# 04B-060.net
KiCad netlist of a schematic drawn in EAGLE
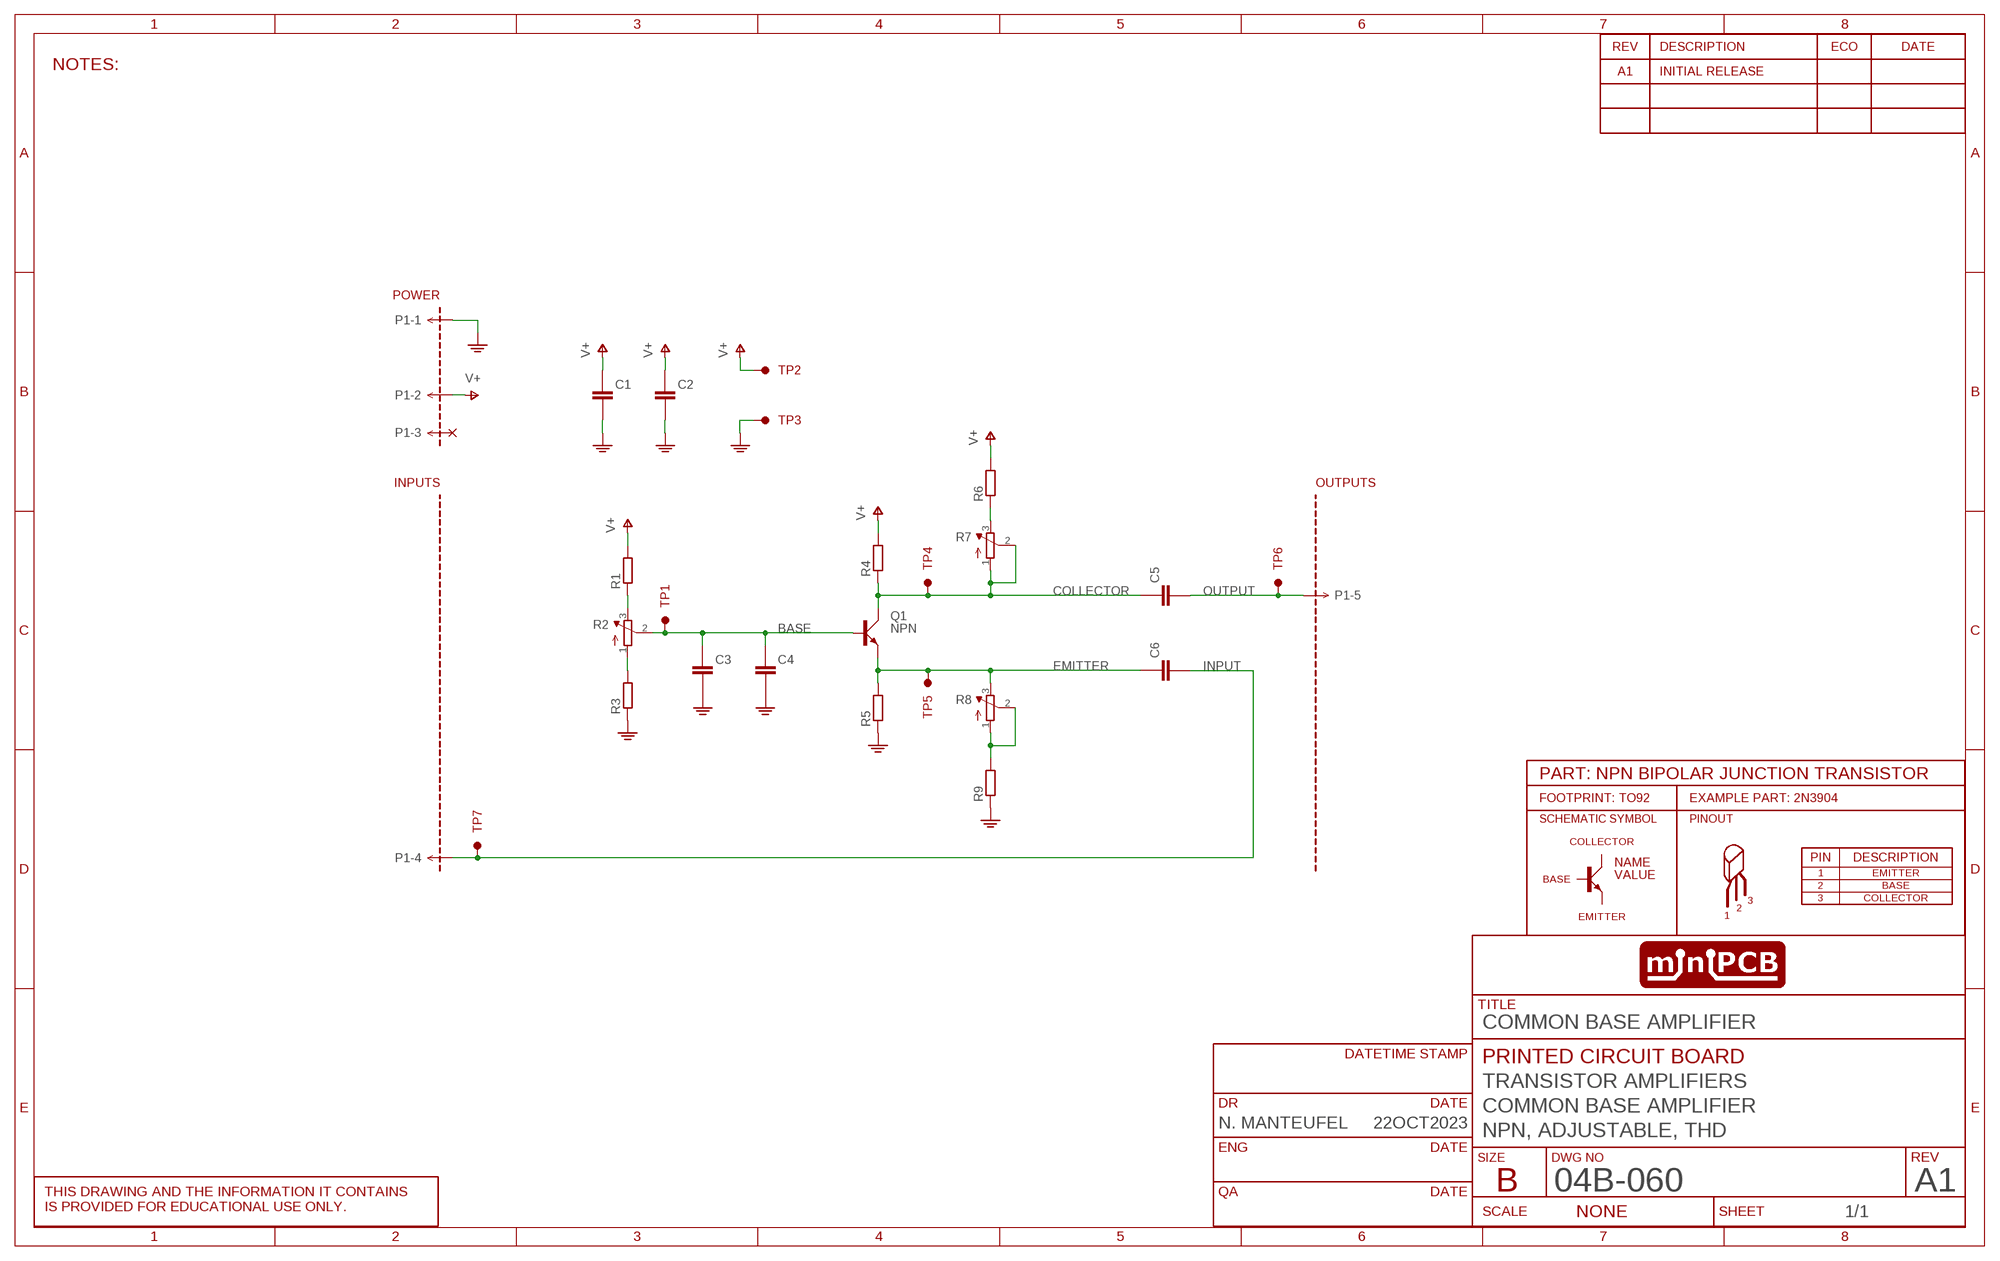
[diagram p0: schematic, sheet 1]

(export (version "E")
  (design (tool "Eeschema 10.0.6"))
  (components
    (comp (ref "C1")
      (value "CAPACITOR_10")
      (footprint "eagle-import:C5MM")
      (libsource (lib "eagle-import") (part "CAPACITOR_10"))
    )
    (comp (ref "C2")
      (value "CAPACITORTHD")
      (footprint "eagle-import:C050-024X044")
      (libsource (lib "eagle-import") (part "CAPACITORTHD"))
    )
    (comp (ref "C3")
      (value "CAPACITOR_10")
      (footprint "eagle-import:C5MM")
      (libsource (lib "eagle-import") (part "CAPACITOR_10"))
    )
    (comp (ref "C4")
      (value "CAPACITORTHD")
      (footprint "eagle-import:C050-024X044")
      (libsource (lib "eagle-import") (part "CAPACITORTHD"))
    )
    (comp (ref "C5")
      (value "CAPACITORTHD")
      (footprint "eagle-import:C050-024X044")
      (libsource (lib "eagle-import") (part "CAPACITORTHD"))
    )
    (comp (ref "C6")
      (value "CAPACITORTHD")
      (footprint "eagle-import:C050-024X044")
      (libsource (lib "eagle-import") (part "CAPACITORTHD"))
    )
    (comp (ref "P1")
      (value "MINIPCB_5P5P")
      (footprint "eagle-import:PINS_1X5")
      (libsource (lib "eagle-import") (part "MINIPCB_5P5P"))
    )
    (comp (ref "PCB1")
      (value "MINIPCB_0P50X50")
      (footprint "eagle-import:MINIPCB_0P_50X50MM")
      (fields
        (field (name "CIRCUIT_CATEGORY") "TRANSISTOR AMPLIFIERS")
        (field (name "PART_NUMBER") "04B-060")
        (field (name "REVISION") "A1-01")
        (field (name "TITLE") "COMMON BASE AMPLIFIER")
      )
      (libsource (lib "eagle-import") (part "MINIPCB_0P50X50"))
    )
    (comp (ref "Q1")
      (value "NPN")
      (footprint "eagle-import:TO92-EBC-OVAL")
      (libsource (lib "eagle-import") (part "BJT_NPNEBC"))
    )
    (comp (ref "R1")
      (value "RESISTORTHD")
      (footprint "eagle-import:0204_10")
      (libsource (lib "eagle-import") (part "RESISTORTHD"))
    )
    (comp (ref "R2")
      (value "TRIMPOT0.100THD")
      (footprint "eagle-import:TRIM_0100")
      (libsource (lib "eagle-import") (part "TRIMPOT0.100THD"))
    )
    (comp (ref "R3")
      (value "RESISTORTHD")
      (footprint "eagle-import:0204_10")
      (libsource (lib "eagle-import") (part "RESISTORTHD"))
    )
    (comp (ref "R4")
      (value "RESISTORTHD")
      (footprint "eagle-import:0204_10")
      (libsource (lib "eagle-import") (part "RESISTORTHD"))
    )
    (comp (ref "R5")
      (value "RESISTORTHD")
      (footprint "eagle-import:0204_10")
      (libsource (lib "eagle-import") (part "RESISTORTHD"))
    )
    (comp (ref "R6")
      (value "RESISTORTHD")
      (footprint "eagle-import:0204_10")
      (libsource (lib "eagle-import") (part "RESISTORTHD"))
    )
    (comp (ref "R7")
      (value "TRIMPOT0.100THD")
      (footprint "eagle-import:TRIM_0100")
      (libsource (lib "eagle-import") (part "TRIMPOT0.100THD"))
    )
    (comp (ref "R8")
      (value "TRIMPOT0.100THD")
      (footprint "eagle-import:TRIM_0100")
      (libsource (lib "eagle-import") (part "TRIMPOT0.100THD"))
    )
    (comp (ref "R9")
      (value "RESISTORTHD")
      (footprint "eagle-import:0204_10")
      (libsource (lib "eagle-import") (part "RESISTORTHD"))
    )
    (comp (ref "TP1")
      (value "TESTPOINTKE5000-SMTEXT")
      (footprint "eagle-import:PINS_1_TESTPOINT_KE5000_NOTEXT")
      (libsource (lib "eagle-import") (part "TESTPOINTKE5000-SMTEXT"))
    )
    (comp (ref "TP2")
      (value "TESTPOINTKE5000-SMTEXT")
      (footprint "eagle-import:PINS_1_TESTPOINT_KE5000_NOTEXT")
      (libsource (lib "eagle-import") (part "TESTPOINTKE5000-SMTEXT"))
    )
    (comp (ref "TP3")
      (value "TESTPOINTKE5000-SMTEXT")
      (footprint "eagle-import:PINS_1_TESTPOINT_KE5000_NOTEXT")
      (libsource (lib "eagle-import") (part "TESTPOINTKE5000-SMTEXT"))
    )
    (comp (ref "TP4")
      (value "TESTPOINTKE5000-SMTEXT")
      (footprint "eagle-import:PINS_1_TESTPOINT_KE5000_NOTEXT")
      (libsource (lib "eagle-import") (part "TESTPOINTKE5000-SMTEXT"))
    )
    (comp (ref "TP5")
      (value "TESTPOINTKE5000-SMTEXT")
      (footprint "eagle-import:PINS_1_TESTPOINT_KE5000_NOTEXT")
      (libsource (lib "eagle-import") (part "TESTPOINTKE5000-SMTEXT"))
    )
    (comp (ref "TP6")
      (value "TESTPOINTKE5000-SMTEXT")
      (footprint "eagle-import:PINS_1_TESTPOINT_KE5000_NOTEXT")
      (libsource (lib "eagle-import") (part "TESTPOINTKE5000-SMTEXT"))
    )
    (comp (ref "TP7")
      (value "TESTPOINTKE5000-SMTEXT")
      (footprint "eagle-import:PINS_1_TESTPOINT_KE5000_NOTEXT")
      (libsource (lib "eagle-import") (part "TESTPOINTKE5000-SMTEXT"))
    )
  )
  (nets
    (net (code "1") (name "/BASE") (class "Default")
      (node (ref "C3") (pin "+") (pinfunction "+_+") (pintype "passive"))
      (node (ref "C4") (pin "1") (pinfunction "+_1") (pintype "passive"))
      (node (ref "Q1") (pin "B") (pinfunction "B_B") (pintype "passive"))
      (node (ref "R2") (pin "2") (pinfunction "S_2") (pintype "passive"))
      (node (ref "TP1") (pin "1") (pinfunction "1_1") (pintype "bidirectional"))
    )
    (net (code "2") (name "/COLLECTOR") (class "Default")
      (node (ref "C5") (pin "1") (pinfunction "+_1") (pintype "passive"))
      (node (ref "Q1") (pin "C") (pinfunction "C_C") (pintype "passive"))
      (node (ref "R4") (pin "1") (pinfunction "1_1") (pintype "passive"))
      (node (ref "R7") (pin "1") (pinfunction "A_1") (pintype "passive"))
      (node (ref "R7") (pin "2") (pinfunction "S_2") (pintype "passive"))
      (node (ref "TP4") (pin "1") (pinfunction "1_1") (pintype "bidirectional"))
    )
    (net (code "3") (name "/EMITTER") (class "Default")
      (node (ref "C6") (pin "1") (pinfunction "+_1") (pintype "passive"))
      (node (ref "Q1") (pin "E") (pinfunction "E_E") (pintype "passive"))
      (node (ref "R5") (pin "2") (pinfunction "2_2") (pintype "passive"))
      (node (ref "R8") (pin "3") (pinfunction "E_3") (pintype "passive"))
      (node (ref "TP5") (pin "1") (pinfunction "1_1") (pintype "bidirectional"))
    )
    (net (code "4") (name "/INPUT") (class "Default")
      (node (ref "C6") (pin "2") (pinfunction "-_2") (pintype "passive"))
      (node (ref "P1") (pin "4") (pinfunction "1_4") (pintype "bidirectional"))
      (node (ref "TP7") (pin "1") (pinfunction "1_1") (pintype "bidirectional"))
    )
    (net (code "5") (name "/OUTPUT") (class "Default")
      (node (ref "C5") (pin "2") (pinfunction "-_2") (pintype "passive"))
      (node (ref "P1") (pin "5") (pinfunction "1_5") (pintype "bidirectional"))
      (node (ref "TP6") (pin "1") (pinfunction "1_1") (pintype "bidirectional"))
    )
    (net (code "6") (name "GND") (class "Default")
      (node (ref "C1") (pin "-") (pinfunction "-_-") (pintype "passive"))
      (node (ref "C2") (pin "2") (pinfunction "-_2") (pintype "passive"))
      (node (ref "C3") (pin "-") (pinfunction "-_-") (pintype "passive"))
      (node (ref "C4") (pin "2") (pinfunction "-_2") (pintype "passive"))
      (node (ref "P1") (pin "1") (pinfunction "1_1") (pintype "bidirectional"))
      (node (ref "R3") (pin "1") (pinfunction "1_1") (pintype "passive"))
      (node (ref "R5") (pin "1") (pinfunction "1_1") (pintype "passive"))
      (node (ref "R9") (pin "1") (pinfunction "1_1") (pintype "passive"))
      (node (ref "TP3") (pin "1") (pinfunction "1_1") (pintype "bidirectional"))
    )
    (net (code "7") (name "Net-(R2-A)") (class "Default")
      (node (ref "R2") (pin "1") (pinfunction "A_1") (pintype "passive"))
      (node (ref "R3") (pin "2") (pinfunction "2_2") (pintype "passive"))
    )
    (net (code "8") (name "Net-(R2-E)") (class "Default")
      (node (ref "R1") (pin "1") (pinfunction "1_1") (pintype "passive"))
      (node (ref "R2") (pin "3") (pinfunction "E_3") (pintype "passive"))
    )
    (net (code "9") (name "Net-(R7-E)") (class "Default")
      (node (ref "R6") (pin "1") (pinfunction "1_1") (pintype "passive"))
      (node (ref "R7") (pin "3") (pinfunction "E_3") (pintype "passive"))
    )
    (net (code "10") (name "Net-(R8-A)") (class "Default")
      (node (ref "R8") (pin "1") (pinfunction "A_1") (pintype "passive"))
      (node (ref "R8") (pin "2") (pinfunction "S_2") (pintype "passive"))
      (node (ref "R9") (pin "2") (pinfunction "2_2") (pintype "passive"))
    )
    (net (code "11") (name "V+") (class "Default")
      (node (ref "C1") (pin "+") (pinfunction "+_+") (pintype "passive"))
      (node (ref "C2") (pin "1") (pinfunction "+_1") (pintype "passive"))
      (node (ref "P1") (pin "2") (pinfunction "1_2") (pintype "bidirectional"))
      (node (ref "R1") (pin "2") (pinfunction "2_2") (pintype "passive"))
      (node (ref "R4") (pin "2") (pinfunction "2_2") (pintype "passive"))
      (node (ref "R6") (pin "2") (pinfunction "2_2") (pintype "passive"))
      (node (ref "TP2") (pin "1") (pinfunction "1_1") (pintype "bidirectional"))
    )
    (net (code "12") (name "unconnected-(P1C-1-Pad3)") (class "Default")
      (node (ref "P1") (pin "3") (pinfunction "1_3") (pintype "bidirectional"))
    )
  )
)
